# power.net
KiCad netlist of a schematic drawn in EAGLE
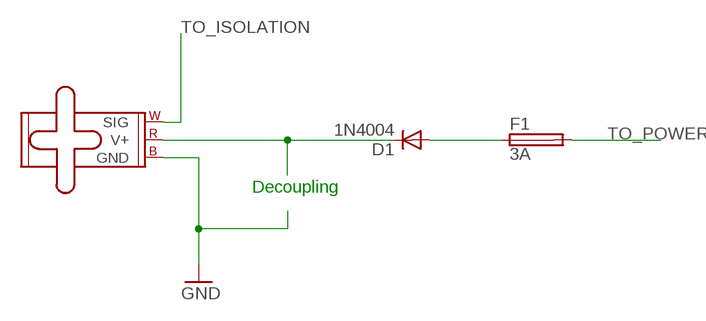
[diagram p0: schematic, sheet 1]

(export (version "E")
  (design (tool "Eeschema 10.0.6"))
  (components
    (comp (ref "D1")
      (value "1N4004")
      (footprint "eagle-import:DO41-10")
      (libsource (lib "eagle-import") (part "1N4004"))
    )
    (comp (ref "F1")
      (value "3A")
      (footprint "eagle-import:TE5")
      (libsource (lib "eagle-import") (part "TE5"))
    )
    (comp (ref "M1")
      (value "SMALL_SERVO")
      (footprint "eagle-import:1X03")
      (libsource (lib "eagle-import") (part "SMALL_SERVO"))
    )
  )
  (nets
    (net (code "1") (name "/TO_ISOLATION") (class "Default")
      (node (ref "M1") (pin "1") (pinfunction "SIG_1") (pintype "bidirectional"))
    )
    (net (code "2") (name "/TO_POWER") (class "Default")
      (node (ref "F1") (pin "2") (pinfunction "2_2") (pintype "passive"))
    )
    (net (code "3") (name "GND") (class "Default")
      (node (ref "M1") (pin "3") (pinfunction "GND_3") (pintype "bidirectional"))
    )
    (net (code "4") (name "Net-(D1-PadA)") (class "Default")
      (node (ref "D1") (pin "A") (pinfunction "A_A") (pintype "passive"))
      (node (ref "F1") (pin "1") (pinfunction "1_1") (pintype "passive"))
    )
    (net (code "5") (name "Net-(M1-V+)") (class "Default")
      (node (ref "D1") (pin "C") (pinfunction "C_C") (pintype "passive"))
      (node (ref "M1") (pin "2") (pinfunction "V+_2") (pintype "bidirectional"))
    )
  )
)
